# ProPrj_New_Project_2026-04-18_10-00-05_2.net
KiCad netlist of a schematic drawn in EasyEDA Pro
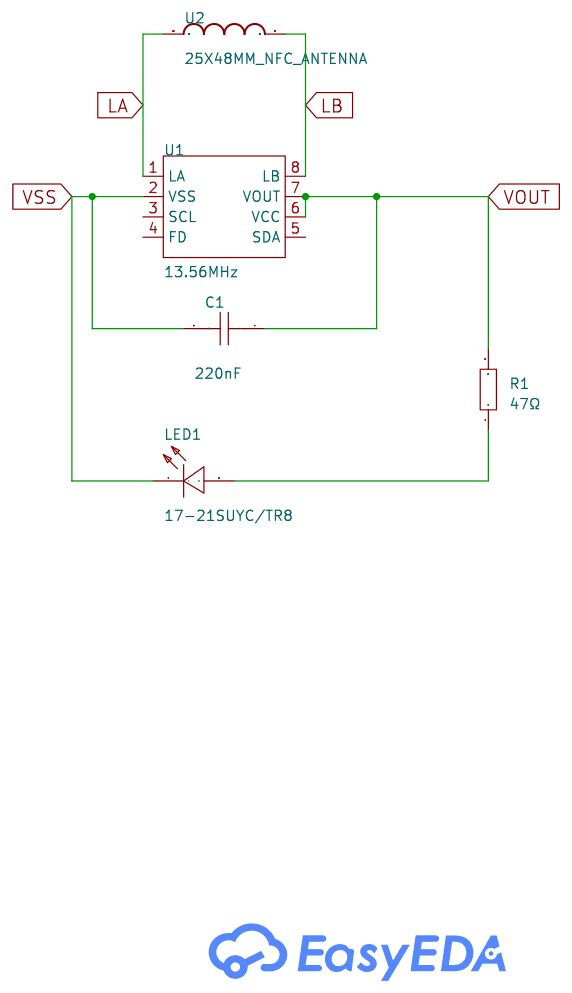
[diagram p0: schematic sheet]

(export (version "E")
  (design (tool "Eeschema 10.0.6"))
  (components
    (comp (ref "C1")
      (value "220nF")
      (footprint "easyedapro:C0603")
      (libsource (lib "easyedapro") (part "CAP"))
    )
    (comp (ref "LED1")
      (value "17-21SUYC/TR8")
      (footprint "easyedapro:LED0805-RD")
      (fields (field (name "Manufacturer") "KENTO"))
      (libsource (lib "easyedapro") (part "17-21SUYC/TR8"))
    )
    (comp (ref "R1") (value "47Ω") (footprint "easyedapro:R0603") (libsource (lib "easyedapro") (part "Res")))
    (comp (ref "U1")
      (value "13.56MHz")
      (footprint "easyedapro:XQFN-8_L1.6-W1.6-P0.50-BL_NT3H2111W0FHKH")
      (fields (field (name "Manufacturer Part") "NT3H2111W0FHKH") (field (name "Manufacturer") "NXP(恩智浦)"))
      (libsource (lib "easyedapro") (part "NT3H2111W0FHKH"))
    )
    (comp (ref "U2")
      (value "25X48MM_NFC_ANTENNA")
      (footprint "easyedapro:25X48MM_NFC_ANTENNA")
      (libsource (lib "easyedapro") (part "25X48MM_NFC_ANTENNA"))
    )
  )
  (nets
    (net (code "1") (name "LA") (class "Default")
      (node (ref "U1") (pin "1") (pinfunction "LA_1") (pintype "unspecified"))
      (node (ref "U2") (pin "P$1") (pinfunction "P$1_P$1") (pintype "bidirectional"))
    )
    (net (code "2") (name "LB") (class "Default")
      (node (ref "U1") (pin "8") (pinfunction "LB_8") (pintype "unspecified"))
      (node (ref "U2") (pin "P$2") (pinfunction "P$2_P$2") (pintype "bidirectional"))
    )
    (net (code "3") (name "Net-(LED1-+)") (class "Default")
      (node (ref "LED1") (pin "2") (pinfunction "+_2") (pintype "input"))
      (node (ref "R1") (pin "1") (pinfunction "1_1") (pintype "input"))
    )
    (net (code "4") (name "VOUT") (class "Default")
      (node (ref "C1") (pin "1") (pinfunction "1_1") (pintype "input"))
      (node (ref "R1") (pin "2") (pinfunction "2_2") (pintype "input"))
      (node (ref "U1") (pin "6") (pinfunction "VCC_6") (pintype "unspecified"))
      (node (ref "U1") (pin "7") (pinfunction "VOUT_7") (pintype "unspecified"))
    )
    (net (code "5") (name "VSS") (class "Default")
      (node (ref "C1") (pin "2") (pinfunction "2_2") (pintype "input"))
      (node (ref "LED1") (pin "1") (pinfunction "-_1") (pintype "input"))
      (node (ref "U1") (pin "2") (pinfunction "VSS_2") (pintype "unspecified"))
    )
    (net (code "6") (name "unconnected-(U1-FD-Pad4)") (class "Default")
      (node (ref "U1") (pin "4") (pinfunction "FD_4") (pintype "unspecified"))
    )
    (net (code "7") (name "unconnected-(U1-SCL-Pad3)") (class "Default")
      (node (ref "U1") (pin "3") (pinfunction "SCL_3") (pintype "unspecified"))
    )
    (net (code "8") (name "unconnected-(U1-SDA-Pad5)") (class "Default")
      (node (ref "U1") (pin "5") (pinfunction "SDA_5") (pintype "unspecified"))
    )
  )
)
